# stm32-v1.net
KiCad netlist of a schematic drawn in EAGLE
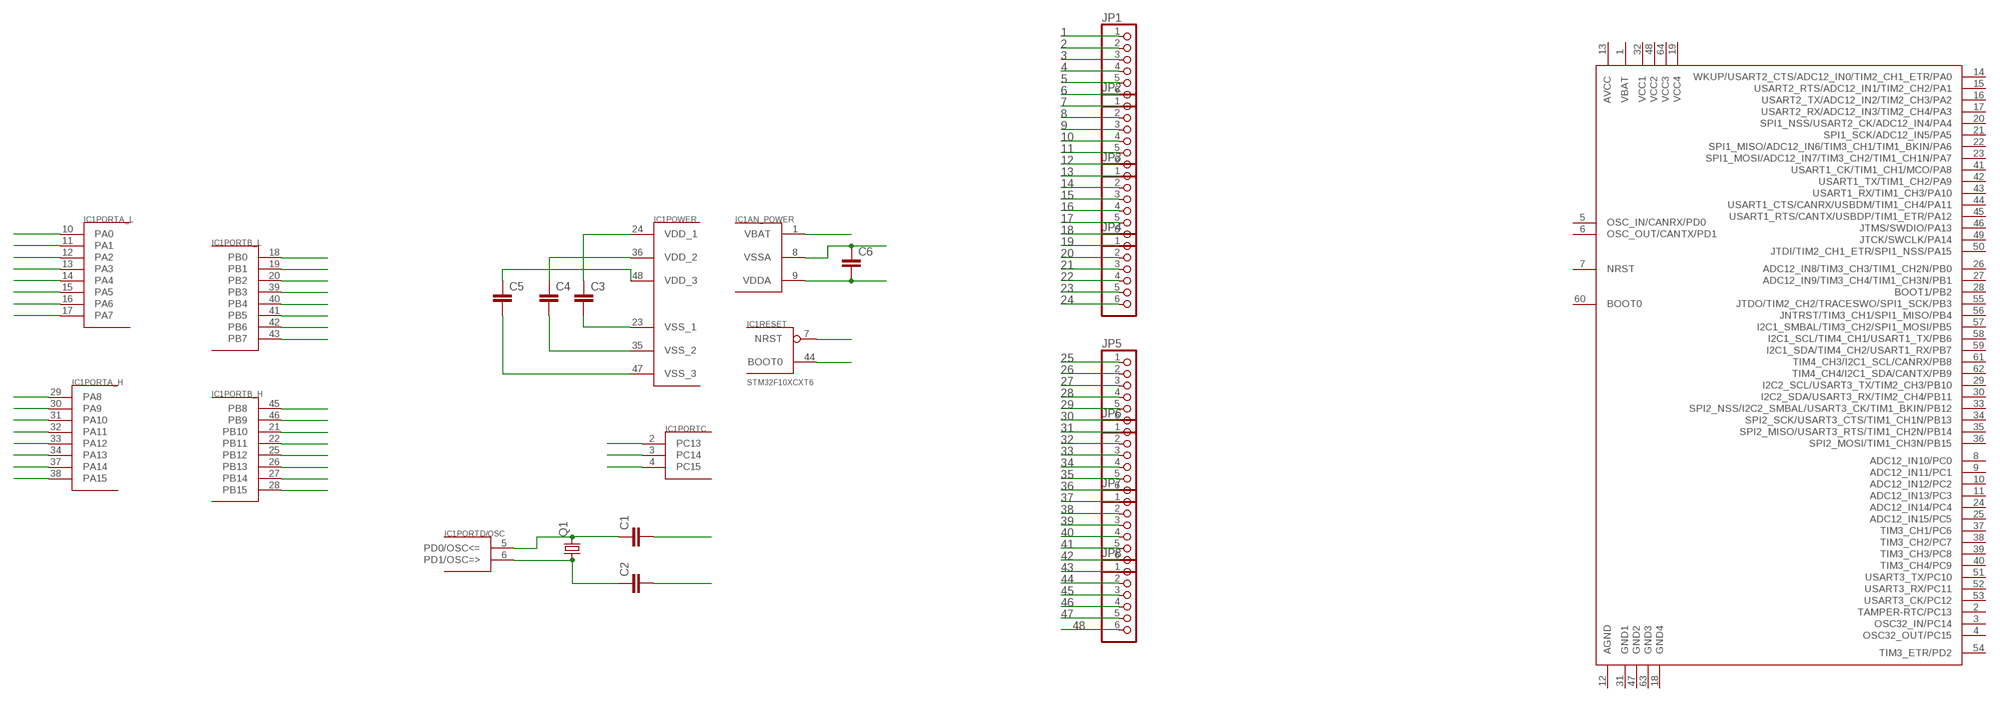
[diagram p0: schematic, sheet 1]

(export (version "E")
  (design (tool "Eeschema 10.0.6"))
  (components
    (comp (ref "C1")
      (value "CAP1206")
      (footprint "eagle-import:1206")
      (libsource (lib "eagle-import") (part "CAP1206"))
    )
    (comp (ref "C2")
      (value "CAP1206")
      (footprint "eagle-import:1206")
      (libsource (lib "eagle-import") (part "CAP1206"))
    )
    (comp (ref "C3")
      (value "CAP1206")
      (footprint "eagle-import:1206")
      (libsource (lib "eagle-import") (part "CAP1206"))
    )
    (comp (ref "C4")
      (value "CAP1206")
      (footprint "eagle-import:1206")
      (libsource (lib "eagle-import") (part "CAP1206"))
    )
    (comp (ref "C5")
      (value "CAP1206")
      (footprint "eagle-import:1206")
      (libsource (lib "eagle-import") (part "CAP1206"))
    )
    (comp (ref "C6")
      (value "CAP1206")
      (footprint "eagle-import:1206")
      (libsource (lib "eagle-import") (part "CAP1206"))
    )
    (comp (ref "IC1")
      (value "STM32F10XCXT6")
      (footprint "eagle-import:TQFP48")
      (libsource (lib "eagle-import") (part "STM32F10XCXT6"))
    )
    (comp (ref "JP1")
      (value "PINHD-1X6")
      (footprint "eagle-import:1X06")
      (libsource (lib "eagle-import") (part "PINHD-1X6"))
    )
    (comp (ref "JP2")
      (value "PINHD-1X6")
      (footprint "eagle-import:1X06")
      (libsource (lib "eagle-import") (part "PINHD-1X6"))
    )
    (comp (ref "JP3")
      (value "PINHD-1X6")
      (footprint "eagle-import:1X06")
      (libsource (lib "eagle-import") (part "PINHD-1X6"))
    )
    (comp (ref "JP4")
      (value "PINHD-1X6")
      (footprint "eagle-import:1X06")
      (libsource (lib "eagle-import") (part "PINHD-1X6"))
    )
    (comp (ref "JP5")
      (value "PINHD-1X6")
      (footprint "eagle-import:1X06")
      (libsource (lib "eagle-import") (part "PINHD-1X6"))
    )
    (comp (ref "JP6")
      (value "PINHD-1X6")
      (footprint "eagle-import:1X06")
      (libsource (lib "eagle-import") (part "PINHD-1X6"))
    )
    (comp (ref "JP7")
      (value "PINHD-1X6")
      (footprint "eagle-import:1X06")
      (libsource (lib "eagle-import") (part "PINHD-1X6"))
    )
    (comp (ref "JP8")
      (value "PINHD-1X6")
      (footprint "eagle-import:1X06")
      (libsource (lib "eagle-import") (part "PINHD-1X6"))
    )
    (comp (ref "Q1")
      (value "CRYSTAL5X3")
      (footprint "eagle-import:CRYSTAL-SMD-5X3")
      (libsource (lib "eagle-import") (part "CRYSTAL5X3"))
    )
    (comp (ref "U$2")
      (value "STM32F103X8/B")
      (footprint "eagle-import:LQFP64")
      (libsource (lib "eagle-import") (part "STM32F103X8/B"))
    )
  )
  (nets
    (net (code "1") (name "/1") (class "Default")
      (node (ref "IC1") (pin "1") (pinfunction "VBAT_1") (pintype "power_in"))
      (node (ref "JP1") (pin "1") (pinfunction "1_1") (pintype "passive"))
    )
    (net (code "2") (name "/2") (class "Default")
      (node (ref "IC1") (pin "2") (pinfunction "PC13_2") (pintype "bidirectional"))
      (node (ref "JP1") (pin "2") (pinfunction "2_2") (pintype "passive"))
    )
    (net (code "3") (name "/3") (class "Default")
      (node (ref "IC1") (pin "3") (pinfunction "PC14_3") (pintype "bidirectional"))
      (node (ref "JP1") (pin "3") (pinfunction "3_3") (pintype "passive"))
    )
    (net (code "4") (name "/4") (class "Default")
      (node (ref "IC1") (pin "4") (pinfunction "PC15_4") (pintype "bidirectional"))
      (node (ref "JP1") (pin "4") (pinfunction "4_4") (pintype "passive"))
    )
    (net (code "5") (name "/5") (class "Default")
      (node (ref "C1") (pin "2") (pinfunction "2_2") (pintype "passive"))
      (node (ref "JP1") (pin "5") (pinfunction "5_5") (pintype "passive"))
    )
    (net (code "6") (name "/6") (class "Default")
      (node (ref "C2") (pin "2") (pinfunction "2_2") (pintype "passive"))
      (node (ref "JP1") (pin "6") (pinfunction "6_6") (pintype "passive"))
    )
    (net (code "7") (name "/7") (class "Default")
      (node (ref "IC1") (pin "7") (pinfunction "NRST_7") (pintype "input"))
      (node (ref "JP2") (pin "1") (pinfunction "1_1") (pintype "passive"))
    )
    (net (code "8") (name "/8") (class "Default")
      (node (ref "C6") (pin "1") (pinfunction "1_1") (pintype "passive"))
      (node (ref "IC1") (pin "8") (pinfunction "VSSA_8") (pintype "power_in"))
      (node (ref "JP2") (pin "2") (pinfunction "2_2") (pintype "passive"))
    )
    (net (code "9") (name "/9") (class "Default")
      (node (ref "C6") (pin "2") (pinfunction "2_2") (pintype "passive"))
      (node (ref "IC1") (pin "9") (pinfunction "VDDA_9") (pintype "power_in"))
      (node (ref "JP2") (pin "3") (pinfunction "3_3") (pintype "passive"))
    )
    (net (code "10") (name "/10") (class "Default")
      (node (ref "IC1") (pin "10") (pinfunction "PA0_10") (pintype "bidirectional"))
      (node (ref "JP2") (pin "4") (pinfunction "4_4") (pintype "passive"))
    )
    (net (code "11") (name "/11") (class "Default")
      (node (ref "IC1") (pin "11") (pinfunction "PA1_11") (pintype "bidirectional"))
      (node (ref "JP2") (pin "5") (pinfunction "5_5") (pintype "passive"))
    )
    (net (code "12") (name "/12") (class "Default")
      (node (ref "IC1") (pin "12") (pinfunction "PA2_12") (pintype "bidirectional"))
      (node (ref "JP2") (pin "6") (pinfunction "6_6") (pintype "passive"))
    )
    (net (code "13") (name "/13") (class "Default")
      (node (ref "IC1") (pin "13") (pinfunction "PA3_13") (pintype "bidirectional"))
      (node (ref "JP3") (pin "1") (pinfunction "1_1") (pintype "passive"))
    )
    (net (code "14") (name "/14") (class "Default")
      (node (ref "IC1") (pin "14") (pinfunction "PA4_14") (pintype "bidirectional"))
      (node (ref "JP3") (pin "2") (pinfunction "2_2") (pintype "passive"))
    )
    (net (code "15") (name "/15") (class "Default")
      (node (ref "IC1") (pin "15") (pinfunction "PA5_15") (pintype "bidirectional"))
      (node (ref "JP3") (pin "3") (pinfunction "3_3") (pintype "passive"))
    )
    (net (code "16") (name "/16") (class "Default")
      (node (ref "IC1") (pin "16") (pinfunction "PA6_16") (pintype "bidirectional"))
      (node (ref "JP3") (pin "4") (pinfunction "4_4") (pintype "passive"))
    )
    (net (code "17") (name "/17") (class "Default")
      (node (ref "IC1") (pin "17") (pinfunction "PA7_17") (pintype "bidirectional"))
      (node (ref "JP3") (pin "5") (pinfunction "5_5") (pintype "passive"))
    )
    (net (code "18") (name "/18") (class "Default")
      (node (ref "IC1") (pin "18") (pinfunction "PB0_18") (pintype "bidirectional"))
      (node (ref "JP3") (pin "6") (pinfunction "6_6") (pintype "passive"))
    )
    (net (code "19") (name "/19") (class "Default")
      (node (ref "IC1") (pin "19") (pinfunction "PB1_19") (pintype "bidirectional"))
      (node (ref "JP4") (pin "1") (pinfunction "1_1") (pintype "passive"))
    )
    (net (code "20") (name "/20") (class "Default")
      (node (ref "IC1") (pin "20") (pinfunction "PB2_20") (pintype "bidirectional"))
      (node (ref "JP4") (pin "2") (pinfunction "2_2") (pintype "passive"))
    )
    (net (code "21") (name "/21") (class "Default")
      (node (ref "IC1") (pin "21") (pinfunction "PB10_21") (pintype "bidirectional"))
      (node (ref "JP4") (pin "3") (pinfunction "3_3") (pintype "passive"))
    )
    (net (code "22") (name "/22") (class "Default")
      (node (ref "IC1") (pin "22") (pinfunction "PB11_22") (pintype "bidirectional"))
      (node (ref "JP4") (pin "4") (pinfunction "4_4") (pintype "passive"))
    )
    (net (code "23") (name "/23") (class "Default")
      (node (ref "C3") (pin "2") (pinfunction "2_2") (pintype "passive"))
      (node (ref "IC1") (pin "23") (pinfunction "VSS_1_23") (pintype "power_in"))
      (node (ref "JP4") (pin "5") (pinfunction "5_5") (pintype "passive"))
    )
    (net (code "24") (name "/24") (class "Default")
      (node (ref "C3") (pin "1") (pinfunction "1_1") (pintype "passive"))
      (node (ref "IC1") (pin "24") (pinfunction "VDD_1_24") (pintype "power_in"))
      (node (ref "JP4") (pin "6") (pinfunction "6_6") (pintype "passive"))
    )
    (net (code "25") (name "/25") (class "Default")
      (node (ref "IC1") (pin "25") (pinfunction "PB12_25") (pintype "bidirectional"))
      (node (ref "JP5") (pin "1") (pinfunction "1_1") (pintype "passive"))
    )
    (net (code "26") (name "/26") (class "Default")
      (node (ref "IC1") (pin "26") (pinfunction "PB13_26") (pintype "bidirectional"))
      (node (ref "JP5") (pin "2") (pinfunction "2_2") (pintype "passive"))
    )
    (net (code "27") (name "/27") (class "Default")
      (node (ref "IC1") (pin "27") (pinfunction "PB14_27") (pintype "bidirectional"))
      (node (ref "JP5") (pin "3") (pinfunction "3_3") (pintype "passive"))
    )
    (net (code "28") (name "/28") (class "Default")
      (node (ref "IC1") (pin "28") (pinfunction "PB15_28") (pintype "bidirectional"))
      (node (ref "JP5") (pin "4") (pinfunction "4_4") (pintype "passive"))
    )
    (net (code "29") (name "/29") (class "Default")
      (node (ref "IC1") (pin "29") (pinfunction "PA8_29") (pintype "bidirectional"))
      (node (ref "JP5") (pin "5") (pinfunction "5_5") (pintype "passive"))
    )
    (net (code "30") (name "/30") (class "Default")
      (node (ref "IC1") (pin "30") (pinfunction "PA9_30") (pintype "bidirectional"))
      (node (ref "JP5") (pin "6") (pinfunction "6_6") (pintype "passive"))
    )
    (net (code "31") (name "/31") (class "Default")
      (node (ref "IC1") (pin "31") (pinfunction "PA10_31") (pintype "bidirectional"))
      (node (ref "JP6") (pin "1") (pinfunction "1_1") (pintype "passive"))
    )
    (net (code "32") (name "/32") (class "Default")
      (node (ref "IC1") (pin "32") (pinfunction "PA11_32") (pintype "bidirectional"))
      (node (ref "JP6") (pin "2") (pinfunction "2_2") (pintype "passive"))
    )
    (net (code "33") (name "/33") (class "Default")
      (node (ref "IC1") (pin "33") (pinfunction "PA12_33") (pintype "bidirectional"))
      (node (ref "JP6") (pin "3") (pinfunction "3_3") (pintype "passive"))
    )
    (net (code "34") (name "/34") (class "Default")
      (node (ref "IC1") (pin "34") (pinfunction "PA13_34") (pintype "bidirectional"))
      (node (ref "JP6") (pin "4") (pinfunction "4_4") (pintype "passive"))
    )
    (net (code "35") (name "/35") (class "Default")
      (node (ref "C4") (pin "2") (pinfunction "2_2") (pintype "passive"))
      (node (ref "IC1") (pin "35") (pinfunction "VSS_2_35") (pintype "power_in"))
      (node (ref "JP6") (pin "5") (pinfunction "5_5") (pintype "passive"))
    )
    (net (code "36") (name "/36") (class "Default")
      (node (ref "C4") (pin "1") (pinfunction "1_1") (pintype "passive"))
      (node (ref "IC1") (pin "36") (pinfunction "VDD_2_36") (pintype "power_in"))
      (node (ref "JP6") (pin "6") (pinfunction "6_6") (pintype "passive"))
    )
    (net (code "37") (name "/37") (class "Default")
      (node (ref "IC1") (pin "37") (pinfunction "PA14_37") (pintype "bidirectional"))
      (node (ref "JP7") (pin "1") (pinfunction "1_1") (pintype "passive"))
    )
    (net (code "38") (name "/38") (class "Default")
      (node (ref "IC1") (pin "38") (pinfunction "PA15_38") (pintype "bidirectional"))
      (node (ref "JP7") (pin "2") (pinfunction "2_2") (pintype "passive"))
    )
    (net (code "39") (name "/39") (class "Default")
      (node (ref "IC1") (pin "39") (pinfunction "PB3_39") (pintype "bidirectional"))
      (node (ref "JP7") (pin "3") (pinfunction "3_3") (pintype "passive"))
    )
    (net (code "40") (name "/40") (class "Default")
      (node (ref "IC1") (pin "40") (pinfunction "PB4_40") (pintype "bidirectional"))
      (node (ref "JP7") (pin "4") (pinfunction "4_4") (pintype "passive"))
    )
    (net (code "41") (name "/41") (class "Default")
      (node (ref "IC1") (pin "41") (pinfunction "PB5_41") (pintype "bidirectional"))
      (node (ref "JP7") (pin "5") (pinfunction "5_5") (pintype "passive"))
    )
    (net (code "42") (name "/42") (class "Default")
      (node (ref "IC1") (pin "42") (pinfunction "PB6_42") (pintype "bidirectional"))
      (node (ref "JP7") (pin "6") (pinfunction "6_6") (pintype "passive"))
    )
    (net (code "43") (name "/43") (class "Default")
      (node (ref "IC1") (pin "43") (pinfunction "PB7_43") (pintype "bidirectional"))
      (node (ref "JP8") (pin "1") (pinfunction "1_1") (pintype "passive"))
    )
    (net (code "44") (name "/44") (class "Default")
      (node (ref "IC1") (pin "44") (pinfunction "BOOT0_44") (pintype "input"))
      (node (ref "JP8") (pin "2") (pinfunction "2_2") (pintype "passive"))
    )
    (net (code "45") (name "/45") (class "Default")
      (node (ref "IC1") (pin "45") (pinfunction "PB8_45") (pintype "bidirectional"))
      (node (ref "JP8") (pin "3") (pinfunction "3_3") (pintype "passive"))
    )
    (net (code "46") (name "/46") (class "Default")
      (node (ref "IC1") (pin "46") (pinfunction "PB9_46") (pintype "bidirectional"))
      (node (ref "JP8") (pin "4") (pinfunction "4_4") (pintype "passive"))
    )
    (net (code "47") (name "/47") (class "Default")
      (node (ref "C5") (pin "2") (pinfunction "2_2") (pintype "passive"))
      (node (ref "IC1") (pin "47") (pinfunction "VSS_3_47") (pintype "power_in"))
      (node (ref "JP8") (pin "5") (pinfunction "5_5") (pintype "passive"))
    )
    (net (code "48") (name "/48") (class "Default")
      (node (ref "C5") (pin "1") (pinfunction "1_1") (pintype "passive"))
      (node (ref "IC1") (pin "48") (pinfunction "VDD_3_48") (pintype "power_in"))
      (node (ref "JP8") (pin "6") (pinfunction "6_6") (pintype "passive"))
    )
    (net (code "49") (name "Net-(IC1G-PD0{slash}OSC<=)") (class "Default")
      (node (ref "C1") (pin "1") (pinfunction "1_1") (pintype "passive"))
      (node (ref "IC1") (pin "5") (pinfunction "PD0/OSC<=_5") (pintype "bidirectional"))
      (node (ref "Q1") (pin "3") (pinfunction "2_3") (pintype "passive"))
    )
    (net (code "50") (name "Net-(IC1G-PD1{slash}OSC=>)") (class "Default")
      (node (ref "C2") (pin "1") (pinfunction "1_1") (pintype "passive"))
      (node (ref "IC1") (pin "6") (pinfunction "PD1/OSC=>_6") (pintype "bidirectional"))
      (node (ref "Q1") (pin "1") (pinfunction "1_1") (pintype "passive"))
    )
    (net (code "51") (name "unconnected-(U$2-ADC12_IN8{slash}TIM3_CH3{slash}TIM1_CH2N{slash}PB0-Pad26)") (class "Default")
      (node (ref "U$2") (pin "26") (pinfunction "ADC12_IN8/TIM3_CH3/TIM1_CH2N/PB0_26") (pintype "bidirectional"))
    )
    (net (code "52") (name "unconnected-(U$2-ADC12_IN9{slash}TIM3_CH4{slash}TIM1_CH3N{slash}PB1-Pad27)") (class "Default")
      (node (ref "U$2") (pin "27") (pinfunction "ADC12_IN9/TIM3_CH4/TIM1_CH3N/PB1_27") (pintype "bidirectional"))
    )
    (net (code "53") (name "unconnected-(U$2-ADC12_IN10{slash}PC0-Pad8)") (class "Default")
      (node (ref "U$2") (pin "8") (pinfunction "ADC12_IN10/PC0_8") (pintype "bidirectional"))
    )
    (net (code "54") (name "unconnected-(U$2-ADC12_IN11{slash}PC1-Pad9)") (class "Default")
      (node (ref "U$2") (pin "9") (pinfunction "ADC12_IN11/PC1_9") (pintype "bidirectional"))
    )
    (net (code "55") (name "unconnected-(U$2-ADC12_IN12{slash}PC2-Pad10)") (class "Default")
      (node (ref "U$2") (pin "10") (pinfunction "ADC12_IN12/PC2_10") (pintype "bidirectional"))
    )
    (net (code "56") (name "unconnected-(U$2-ADC12_IN13{slash}PC3-Pad11)") (class "Default")
      (node (ref "U$2") (pin "11") (pinfunction "ADC12_IN13/PC3_11") (pintype "bidirectional"))
    )
    (net (code "57") (name "unconnected-(U$2-ADC12_IN14{slash}PC4-Pad24)") (class "Default")
      (node (ref "U$2") (pin "24") (pinfunction "ADC12_IN14/PC4_24") (pintype "bidirectional"))
    )
    (net (code "58") (name "unconnected-(U$2-ADC12_IN15{slash}PC5-Pad25)") (class "Default")
      (node (ref "U$2") (pin "25") (pinfunction "ADC12_IN15/PC5_25") (pintype "bidirectional"))
    )
    (net (code "59") (name "unconnected-(U$2-AGND-Pad12)") (class "Default")
      (node (ref "U$2") (pin "12") (pinfunction "AGND_12") (pintype "bidirectional"))
    )
    (net (code "60") (name "unconnected-(U$2-AVCC-Pad13)") (class "Default")
      (node (ref "U$2") (pin "13") (pinfunction "AVCC_13") (pintype "bidirectional"))
    )
    (net (code "61") (name "unconnected-(U$2-BOOT0-Pad60)") (class "Default")
      (node (ref "U$2") (pin "60") (pinfunction "BOOT0_60") (pintype "bidirectional"))
    )
    (net (code "62") (name "unconnected-(U$2-BOOT1{slash}PB2-Pad28)") (class "Default")
      (node (ref "U$2") (pin "28") (pinfunction "BOOT1/PB2_28") (pintype "bidirectional"))
    )
    (net (code "63") (name "unconnected-(U$2-GND1-Pad31)") (class "Default")
      (node (ref "U$2") (pin "31") (pinfunction "GND1_31") (pintype "bidirectional"))
    )
    (net (code "64") (name "unconnected-(U$2-GND2-Pad47)") (class "Default")
      (node (ref "U$2") (pin "47") (pinfunction "GND2_47") (pintype "bidirectional"))
    )
    (net (code "65") (name "unconnected-(U$2-GND3-Pad63)") (class "Default")
      (node (ref "U$2") (pin "63") (pinfunction "GND3_63") (pintype "bidirectional"))
    )
    (net (code "66") (name "unconnected-(U$2-GND4-Pad18)") (class "Default")
      (node (ref "U$2") (pin "18") (pinfunction "GND4_18") (pintype "bidirectional"))
    )
    (net (code "67") (name "unconnected-(U$2-I2C1_SCL{slash}TIM4_CH1{slash}USART1_TX{slash}PB6-Pad58)") (class "Default")
      (node (ref "U$2") (pin "58") (pinfunction "I2C1_SCL/TIM4_CH1/USART1_TX/PB6_58") (pintype "bidirectional"))
    )
    (net (code "68") (name "unconnected-(U$2-I2C1_SDA{slash}TIM4_CH2{slash}USART1_RX{slash}PB7-Pad59)") (class "Default")
      (node (ref "U$2") (pin "59") (pinfunction "I2C1_SDA/TIM4_CH2/USART1_RX/PB7_59") (pintype "bidirectional"))
    )
    (net (code "69") (name "unconnected-(U$2-I2C1_SMBAL{slash}TIM3_CH2{slash}SPI1_MOSI{slash}PB5-Pad57)") (class "Default")
      (node (ref "U$2") (pin "57") (pinfunction "I2C1_SMBAL/TIM3_CH2/SPI1_MOSI/PB5_57") (pintype "bidirectional"))
    )
    (net (code "70") (name "unconnected-(U$2-I2C2_SCL{slash}USART3_TX{slash}TIM2_CH3{slash}PB10-Pad29)") (class "Default")
      (node (ref "U$2") (pin "29") (pinfunction "I2C2_SCL/USART3_TX/TIM2_CH3/PB10_29") (pintype "bidirectional"))
    )
    (net (code "71") (name "unconnected-(U$2-I2C2_SDA{slash}USART3_RX{slash}TIM2_CH4{slash}PB11-Pad30)") (class "Default")
      (node (ref "U$2") (pin "30") (pinfunction "I2C2_SDA/USART3_RX/TIM2_CH4/PB11_30") (pintype "bidirectional"))
    )
    (net (code "72") (name "unconnected-(U$2-JNTRST{slash}TIM3_CH1{slash}SPI1_MISO{slash}PB4-Pad56)") (class "Default")
      (node (ref "U$2") (pin "56") (pinfunction "JNTRST/TIM3_CH1/SPI1_MISO/PB4_56") (pintype "bidirectional"))
    )
    (net (code "73") (name "unconnected-(U$2-JTCK{slash}SWCLK{slash}PA14-Pad49)") (class "Default")
      (node (ref "U$2") (pin "49") (pinfunction "JTCK/SWCLK/PA14_49") (pintype "bidirectional"))
    )
    (net (code "74") (name "unconnected-(U$2-JTDI{slash}TIM2_CH1_ETR{slash}SPI1_NSS{slash}PA15-Pad50)") (class "Default")
      (node (ref "U$2") (pin "50") (pinfunction "JTDI/TIM2_CH1_ETR/SPI1_NSS/PA15_50") (pintype "bidirectional"))
    )
    (net (code "75") (name "unconnected-(U$2-JTDO{slash}TIM2_CH2{slash}TRACESWO{slash}SPI1_SCK{slash}PB3-Pad55)") (class "Default")
      (node (ref "U$2") (pin "55") (pinfunction "JTDO/TIM2_CH2/TRACESWO/SPI1_SCK/PB3_55") (pintype "bidirectional"))
    )
    (net (code "76") (name "unconnected-(U$2-JTMS{slash}SWDIO{slash}PA13-Pad46)") (class "Default")
      (node (ref "U$2") (pin "46") (pinfunction "JTMS/SWDIO/PA13_46") (pintype "bidirectional"))
    )
    (net (code "77") (name "unconnected-(U$2-NRST-Pad7)") (class "Default")
      (node (ref "U$2") (pin "7") (pinfunction "NRST_7") (pintype "bidirectional"))
    )
    (net (code "78") (name "unconnected-(U$2-OSC32_IN{slash}PC14-Pad3)") (class "Default")
      (node (ref "U$2") (pin "3") (pinfunction "OSC32_IN/PC14_3") (pintype "bidirectional"))
    )
    (net (code "79") (name "unconnected-(U$2-OSC32_OUT{slash}PC15-Pad4)") (class "Default")
      (node (ref "U$2") (pin "4") (pinfunction "OSC32_OUT/PC15_4") (pintype "bidirectional"))
    )
    (net (code "80") (name "unconnected-(U$2-OSC_IN{slash}CANRX{slash}PD0-Pad5)") (class "Default")
      (node (ref "U$2") (pin "5") (pinfunction "OSC_IN/CANRX/PD0_5") (pintype "bidirectional"))
    )
    (net (code "81") (name "unconnected-(U$2-OSC_OUT{slash}CANTX{slash}PD1-Pad6)") (class "Default")
      (node (ref "U$2") (pin "6") (pinfunction "OSC_OUT/CANTX/PD1_6") (pintype "bidirectional"))
    )
    (net (code "82") (name "unconnected-(U$2-SPI1_MISO{slash}ADC12_IN6{slash}TIM3_CH1{slash}TIM1_BKIN{slash}PA6-Pad22)") (class "Default")
      (node (ref "U$2") (pin "22") (pinfunction "SPI1_MISO/ADC12_IN6/TIM3_CH1/TIM1_BKIN/PA6_22") (pintype "bidirectional"))
    )
    (net (code "83") (name "unconnected-(U$2-SPI1_MOSI{slash}ADC12_IN7{slash}TIM3_CH2{slash}TIM1_CH1N{slash}PA7-Pad23)") (class "Default")
      (node (ref "U$2") (pin "23") (pinfunction "SPI1_MOSI/ADC12_IN7/TIM3_CH2/TIM1_CH1N/PA7_23") (pintype "bidirectional"))
    )
    (net (code "84") (name "unconnected-(U$2-SPI1_NSS{slash}USART2_CK{slash}ADC12_IN4{slash}PA4-Pad20)") (class "Default")
      (node (ref "U$2") (pin "20") (pinfunction "SPI1_NSS/USART2_CK/ADC12_IN4/PA4_20") (pintype "bidirectional"))
    )
    (net (code "85") (name "unconnected-(U$2-SPI1_SCK{slash}ADC12_IN5{slash}PA5-Pad21)") (class "Default")
      (node (ref "U$2") (pin "21") (pinfunction "SPI1_SCK/ADC12_IN5/PA5_21") (pintype "bidirectional"))
    )
    (net (code "86") (name "unconnected-(U$2-SPI2_MISO{slash}USART3_RTS{slash}TIM1_CH2N{slash}PB14-Pad35)") (class "Default")
      (node (ref "U$2") (pin "35") (pinfunction "SPI2_MISO/USART3_RTS/TIM1_CH2N/PB14_35") (pintype "bidirectional"))
    )
    (net (code "87") (name "unconnected-(U$2-SPI2_MOSI{slash}TIM1_CH3N{slash}PB15-Pad36)") (class "Default")
      (node (ref "U$2") (pin "36") (pinfunction "SPI2_MOSI/TIM1_CH3N/PB15_36") (pintype "bidirectional"))
    )
    (net (code "88") (name "unconnected-(U$2-SPI2_NSS{slash}I2C2_SMBAL{slash}USART3_CK{slash}TIM1_BKIN{slash}PB12-Pad33)") (class "Default")
      (node (ref "U$2") (pin "33") (pinfunction "SPI2_NSS/I2C2_SMBAL/USART3_CK/TIM1_BKIN/PB12_33") (pintype "bidirectional"))
    )
    (net (code "89") (name "unconnected-(U$2-SPI2_SCK{slash}USART3_CTS{slash}TIM1_CH1N{slash}PB13-Pad34)") (class "Default")
      (node (ref "U$2") (pin "34") (pinfunction "SPI2_SCK/USART3_CTS/TIM1_CH1N/PB13_34") (pintype "bidirectional"))
    )
    (net (code "90") (name "unconnected-(U$2-TAMPER-RTC{slash}PC13-Pad2)") (class "Default")
      (node (ref "U$2") (pin "2") (pinfunction "TAMPER-RTC/PC13_2") (pintype "bidirectional"))
    )
    (net (code "91") (name "unconnected-(U$2-TIM3_CH1{slash}PC6-Pad37)") (class "Default")
      (node (ref "U$2") (pin "37") (pinfunction "TIM3_CH1/PC6_37") (pintype "bidirectional"))
    )
    (net (code "92") (name "unconnected-(U$2-TIM3_CH2{slash}PC7-Pad38)") (class "Default")
      (node (ref "U$2") (pin "38") (pinfunction "TIM3_CH2/PC7_38") (pintype "bidirectional"))
    )
    (net (code "93") (name "unconnected-(U$2-TIM3_CH3{slash}PC8-Pad39)") (class "Default")
      (node (ref "U$2") (pin "39") (pinfunction "TIM3_CH3/PC8_39") (pintype "bidirectional"))
    )
    (net (code "94") (name "unconnected-(U$2-TIM3_CH4{slash}PC9-Pad40)") (class "Default")
      (node (ref "U$2") (pin "40") (pinfunction "TIM3_CH4/PC9_40") (pintype "bidirectional"))
    )
    (net (code "95") (name "unconnected-(U$2-TIM3_ETR{slash}PD2-Pad54)") (class "Default")
      (node (ref "U$2") (pin "54") (pinfunction "TIM3_ETR/PD2_54") (pintype "bidirectional"))
    )
    (net (code "96") (name "unconnected-(U$2-TIM4_CH3{slash}I2C1_SCL{slash}CANRX{slash}PB8-Pad61)") (class "Default")
      (node (ref "U$2") (pin "61") (pinfunction "TIM4_CH3/I2C1_SCL/CANRX/PB8_61") (pintype "bidirectional"))
    )
    (net (code "97") (name "unconnected-(U$2-TIM4_CH4{slash}I2C1_SDA{slash}CANTX{slash}PB9-Pad62)") (class "Default")
      (node (ref "U$2") (pin "62") (pinfunction "TIM4_CH4/I2C1_SDA/CANTX/PB9_62") (pintype "bidirectional"))
    )
    (net (code "98") (name "unconnected-(U$2-USART1_CK{slash}TIM1_CH1{slash}MCO{slash}PA8-Pad41)") (class "Default")
      (node (ref "U$2") (pin "41") (pinfunction "USART1_CK/TIM1_CH1/MCO/PA8_41") (pintype "bidirectional"))
    )
    (net (code "99") (name "unconnected-(U$2-USART1_CTS{slash}CANRX{slash}USBDM{slash}TIM1_CH4{slash}PA11-Pad44)") (class "Default")
      (node (ref "U$2") (pin "44") (pinfunction "USART1_CTS/CANRX/USBDM/TIM1_CH4/PA11_44") (pintype "bidirectional"))
    )
    (net (code "100") (name "unconnected-(U$2-USART1_RTS{slash}CANTX{slash}USBDP{slash}TIM1_ETR{slash}PA12-Pad45)") (class "Default")
      (node (ref "U$2") (pin "45") (pinfunction "USART1_RTS/CANTX/USBDP/TIM1_ETR/PA12_45") (pintype "bidirectional"))
    )
    (net (code "101") (name "unconnected-(U$2-USART1_RX{slash}TIM1_CH3{slash}PA10-Pad43)") (class "Default")
      (node (ref "U$2") (pin "43") (pinfunction "USART1_RX/TIM1_CH3/PA10_43") (pintype "bidirectional"))
    )
    (net (code "102") (name "unconnected-(U$2-USART1_TX{slash}TIM1_CH2{slash}PA9-Pad42)") (class "Default")
      (node (ref "U$2") (pin "42") (pinfunction "USART1_TX/TIM1_CH2/PA9_42") (pintype "bidirectional"))
    )
    (net (code "103") (name "unconnected-(U$2-USART2_RTS{slash}ADC12_IN1{slash}TIM2_CH2{slash}PA1-Pad15)") (class "Default")
      (node (ref "U$2") (pin "15") (pinfunction "USART2_RTS/ADC12_IN1/TIM2_CH2/PA1_15") (pintype "bidirectional"))
    )
    (net (code "104") (name "unconnected-(U$2-USART2_RX{slash}ADC12_IN3{slash}TIM2_CH4{slash}PA3-Pad17)") (class "Default")
      (node (ref "U$2") (pin "17") (pinfunction "USART2_RX/ADC12_IN3/TIM2_CH4/PA3_17") (pintype "bidirectional"))
    )
    (net (code "105") (name "unconnected-(U$2-USART2_TX{slash}ADC12_IN2{slash}TIM2_CH3{slash}PA2-Pad16)") (class "Default")
      (node (ref "U$2") (pin "16") (pinfunction "USART2_TX/ADC12_IN2/TIM2_CH3/PA2_16") (pintype "bidirectional"))
    )
    (net (code "106") (name "unconnected-(U$2-USART3_CK{slash}PC12-Pad53)") (class "Default")
      (node (ref "U$2") (pin "53") (pinfunction "USART3_CK/PC12_53") (pintype "bidirectional"))
    )
    (net (code "107") (name "unconnected-(U$2-USART3_RX{slash}PC11-Pad52)") (class "Default")
      (node (ref "U$2") (pin "52") (pinfunction "USART3_RX/PC11_52") (pintype "bidirectional"))
    )
    (net (code "108") (name "unconnected-(U$2-USART3_TX{slash}PC10-Pad51)") (class "Default")
      (node (ref "U$2") (pin "51") (pinfunction "USART3_TX/PC10_51") (pintype "bidirectional"))
    )
    (net (code "109") (name "unconnected-(U$2-VBAT-Pad1)") (class "Default")
      (node (ref "U$2") (pin "1") (pinfunction "VBAT_1") (pintype "bidirectional"))
    )
    (net (code "110") (name "unconnected-(U$2-VCC1-Pad32)") (class "Default")
      (node (ref "U$2") (pin "32") (pinfunction "VCC1_32") (pintype "bidirectional"))
    )
    (net (code "111") (name "unconnected-(U$2-VCC2-Pad48)") (class "Default")
      (node (ref "U$2") (pin "48") (pinfunction "VCC2_48") (pintype "bidirectional"))
    )
    (net (code "112") (name "unconnected-(U$2-VCC3-Pad64)") (class "Default")
      (node (ref "U$2") (pin "64") (pinfunction "VCC3_64") (pintype "bidirectional"))
    )
    (net (code "113") (name "unconnected-(U$2-VCC4-Pad19)") (class "Default")
      (node (ref "U$2") (pin "19") (pinfunction "VCC4_19") (pintype "bidirectional"))
    )
    (net (code "114") (name "unconnected-(U$2-WKUP{slash}USART2_CTS{slash}ADC12_IN0{slash}TIM2_CH1_ETR{slash}PA0-Pad14)") (class "Default")
      (node (ref "U$2") (pin "14") (pinfunction "WKUP/USART2_CTS/ADC12_IN0/TIM2_CH1_ETR/PA0_14") (pintype "bidirectional"))
    )
  )
)
